# new_full.net
KiCad netlist of a schematic drawn in EAGLE
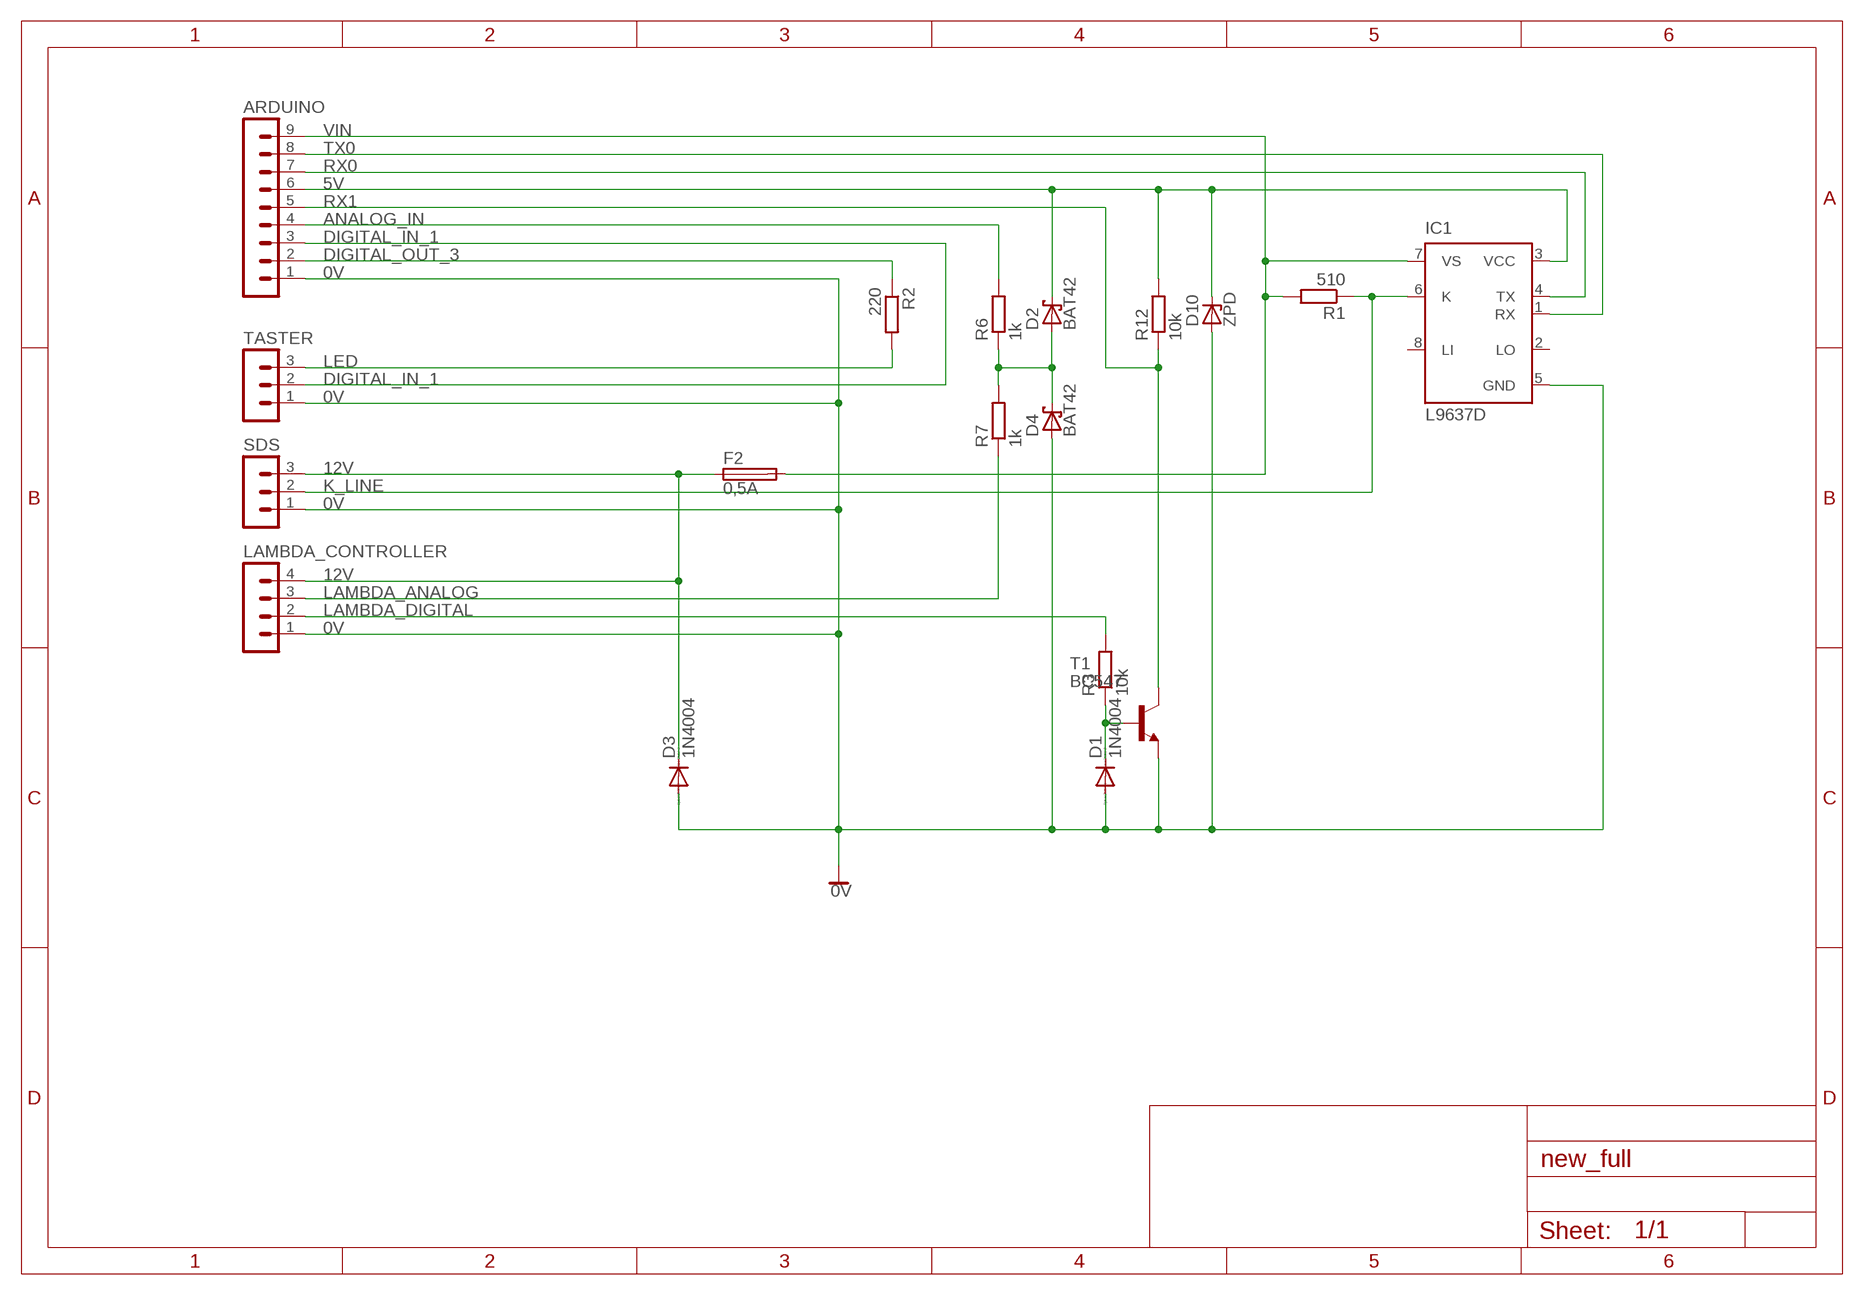
[diagram p0: schematic, sheet 1]

(export (version "E")
  (design (tool "Eeschema 10.0.6"))
  (components
    (comp (ref "ARDUINO")
      (value "MA09-1")
      (footprint "eagle-import:MA09-1")
      (libsource (lib "eagle-import") (part "MA09-1"))
    )
    (comp (ref "D1")
      (value "1N4004")
      (footprint "eagle-import:DO41-10")
      (libsource (lib "eagle-import") (part "1N4004"))
    )
    (comp (ref "D2")
      (value "BAT42")
      (footprint "eagle-import:DO35-10")
      (libsource (lib "eagle-import") (part "BAT42"))
    )
    (comp (ref "D3")
      (value "1N4004")
      (footprint "eagle-import:DO41-10")
      (libsource (lib "eagle-import") (part "1N4004"))
    )
    (comp (ref "D4")
      (value "BAT42")
      (footprint "eagle-import:DO35-10")
      (libsource (lib "eagle-import") (part "BAT42"))
    )
    (comp (ref "D10")
      (value "ZPD")
      (footprint "eagle-import:DO35Z10")
      (libsource (lib "eagle-import") (part "ZPD"))
    )
    (comp (ref "F2")
      (value "0,5A")
      (footprint "eagle-import:SH22,5")
      (fields (field (name "MF") "SCHURTER") (field (name "MPN") "0031.8201"))
      (libsource (lib "eagle-import") (part "SH22,5"))
    )
    (comp (ref "IC1")
      (value "L9637D")
      (footprint "eagle-import:SO08")
      (libsource (lib "eagle-import") (part "L9637D"))
    )
    (comp (ref "LAMBDA_CONTROLLER")
      (value "MA04-1")
      (footprint "eagle-import:MA04-1")
      (libsource (lib "eagle-import") (part "MA04-1"))
    )
    (comp (ref "R1")
      (value "510")
      (footprint "eagle-import:0207_7")
      (libsource (lib "eagle-import") (part "R-EU_0207/7"))
    )
    (comp (ref "R2")
      (value "220")
      (footprint "eagle-import:0207_7")
      (libsource (lib "eagle-import") (part "R-EU_0207/7"))
    )
    (comp (ref "R3")
      (value "10k")
      (footprint "eagle-import:0207_7")
      (libsource (lib "eagle-import") (part "R-EU_0207/7"))
    )
    (comp (ref "R6")
      (value "1k")
      (footprint "eagle-import:0207_7")
      (libsource (lib "eagle-import") (part "R-EU_0207/7"))
    )
    (comp (ref "R7")
      (value "1k")
      (footprint "eagle-import:0207_7")
      (libsource (lib "eagle-import") (part "R-EU_0207/7"))
    )
    (comp (ref "R12")
      (value "10k")
      (footprint "eagle-import:0207_7")
      (libsource (lib "eagle-import") (part "R-EU_0207/7"))
    )
    (comp (ref "SDS")
      (value "MA03-1")
      (footprint "eagle-import:MA03-1")
      (libsource (lib "eagle-import") (part "MA03-1"))
    )
    (comp (ref "T1")
      (value "BC547")
      (footprint "eagle-import:TO92")
      (libsource (lib "eagle-import") (part "BC547"))
    )
    (comp (ref "TASTER")
      (value "MA03-1")
      (footprint "eagle-import:MA03-1")
      (libsource (lib "eagle-import") (part "MA03-1"))
    )
  )
  (nets
    (net (code "1") (name "/5V") (class "Default")
      (node (ref "ARDUINO") (pin "6") (pinfunction "6_6") (pintype "passive"))
      (node (ref "D10") (pin "C") (pinfunction "C_C") (pintype "passive"))
      (node (ref "D2") (pin "C") (pinfunction "C_C") (pintype "passive"))
      (node (ref "IC1") (pin "3") (pinfunction "VCC_3") (pintype "power_in"))
      (node (ref "R12") (pin "2") (pinfunction "2_2") (pintype "passive"))
    )
    (net (code "2") (name "/12V") (class "Default")
      (node (ref "D3") (pin "C") (pinfunction "C_C") (pintype "passive"))
      (node (ref "F2") (pin "1") (pinfunction "1_1") (pintype "passive"))
      (node (ref "LAMBDA_CONTROLLER") (pin "4") (pinfunction "4_4") (pintype "passive"))
      (node (ref "SDS") (pin "3") (pinfunction "3_3") (pintype "passive"))
    )
    (net (code "3") (name "/ANALOG_IN") (class "Default")
      (node (ref "ARDUINO") (pin "4") (pinfunction "4_4") (pintype "passive"))
      (node (ref "D2") (pin "A") (pinfunction "A_A") (pintype "passive"))
      (node (ref "D4") (pin "C") (pinfunction "C_C") (pintype "passive"))
      (node (ref "R6") (pin "1") (pinfunction "1_1") (pintype "passive"))
      (node (ref "R6") (pin "2") (pinfunction "2_2") (pintype "passive"))
      (node (ref "R7") (pin "2") (pinfunction "2_2") (pintype "passive"))
    )
    (net (code "4") (name "/DIGITAL_IN_1") (class "Default")
      (node (ref "ARDUINO") (pin "3") (pinfunction "3_3") (pintype "passive"))
      (node (ref "TASTER") (pin "2") (pinfunction "2_2") (pintype "passive"))
    )
    (net (code "5") (name "/DIGITAL_OUT_3") (class "Default")
      (node (ref "ARDUINO") (pin "2") (pinfunction "2_2") (pintype "passive"))
      (node (ref "R2") (pin "1") (pinfunction "1_1") (pintype "passive"))
    )
    (net (code "6") (name "/K_LINE") (class "Default")
      (node (ref "IC1") (pin "6") (pinfunction "K_6") (pintype "input"))
      (node (ref "R1") (pin "1") (pinfunction "1_1") (pintype "passive"))
      (node (ref "SDS") (pin "2") (pinfunction "2_2") (pintype "passive"))
    )
    (net (code "7") (name "/LAMBDA_ANALOG") (class "Default")
      (node (ref "LAMBDA_CONTROLLER") (pin "3") (pinfunction "3_3") (pintype "passive"))
      (node (ref "R7") (pin "1") (pinfunction "1_1") (pintype "passive"))
    )
    (net (code "8") (name "/LAMBDA_DIGITAL") (class "Default")
      (node (ref "LAMBDA_CONTROLLER") (pin "2") (pinfunction "2_2") (pintype "passive"))
      (node (ref "R3") (pin "2") (pinfunction "2_2") (pintype "passive"))
    )
    (net (code "9") (name "/LED") (class "Default")
      (node (ref "R2") (pin "2") (pinfunction "2_2") (pintype "passive"))
      (node (ref "TASTER") (pin "3") (pinfunction "3_3") (pintype "passive"))
    )
    (net (code "10") (name "/RX0") (class "Default")
      (node (ref "ARDUINO") (pin "7") (pinfunction "7_7") (pintype "passive"))
      (node (ref "IC1") (pin "4") (pinfunction "TX_4") (pintype "input"))
    )
    (net (code "11") (name "/RX1") (class "Default")
      (node (ref "ARDUINO") (pin "5") (pinfunction "5_5") (pintype "passive"))
      (node (ref "R12") (pin "1") (pinfunction "1_1") (pintype "passive"))
      (node (ref "T1") (pin "3") (pinfunction "C_3") (pintype "passive"))
    )
    (net (code "12") (name "/TX0") (class "Default")
      (node (ref "ARDUINO") (pin "8") (pinfunction "8_8") (pintype "passive"))
      (node (ref "IC1") (pin "1") (pinfunction "RX_1") (pintype "output"))
    )
    (net (code "13") (name "/VIN") (class "Default")
      (node (ref "ARDUINO") (pin "9") (pinfunction "9_9") (pintype "passive"))
      (node (ref "F2") (pin "2") (pinfunction "2_2") (pintype "passive"))
      (node (ref "IC1") (pin "7") (pinfunction "VS_7") (pintype "power_in"))
      (node (ref "R1") (pin "2") (pinfunction "2_2") (pintype "passive"))
    )
    (net (code "14") (name "0V") (class "Default")
      (node (ref "ARDUINO") (pin "1") (pinfunction "1_1") (pintype "passive"))
      (node (ref "D1") (pin "A") (pinfunction "A_A") (pintype "passive"))
      (node (ref "D10") (pin "A") (pinfunction "A_A") (pintype "passive"))
      (node (ref "D3") (pin "A") (pinfunction "A_A") (pintype "passive"))
      (node (ref "D4") (pin "A") (pinfunction "A_A") (pintype "passive"))
      (node (ref "IC1") (pin "5") (pinfunction "GND_5") (pintype "power_in"))
      (node (ref "LAMBDA_CONTROLLER") (pin "1") (pinfunction "1_1") (pintype "passive"))
      (node (ref "SDS") (pin "1") (pinfunction "1_1") (pintype "passive"))
      (node (ref "T1") (pin "1") (pinfunction "E_1") (pintype "passive"))
      (node (ref "TASTER") (pin "1") (pinfunction "1_1") (pintype "passive"))
    )
    (net (code "15") (name "Net-(T1-B)") (class "Default")
      (node (ref "D1") (pin "C") (pinfunction "C_C") (pintype "passive"))
      (node (ref "R3") (pin "1") (pinfunction "1_1") (pintype "passive"))
      (node (ref "T1") (pin "2") (pinfunction "B_2") (pintype "passive"))
    )
    (net (code "16") (name "unconnected-(IC1-LI-Pad8)") (class "Default")
      (node (ref "IC1") (pin "8") (pinfunction "LI_8") (pintype "input"))
    )
    (net (code "17") (name "unconnected-(IC1-LO-Pad2)") (class "Default")
      (node (ref "IC1") (pin "2") (pinfunction "LO_2") (pintype "output"))
    )
  )
)
